# SchematicPowerSupply_V1.net
KiCad netlist of a schematic drawn in Altium Designer
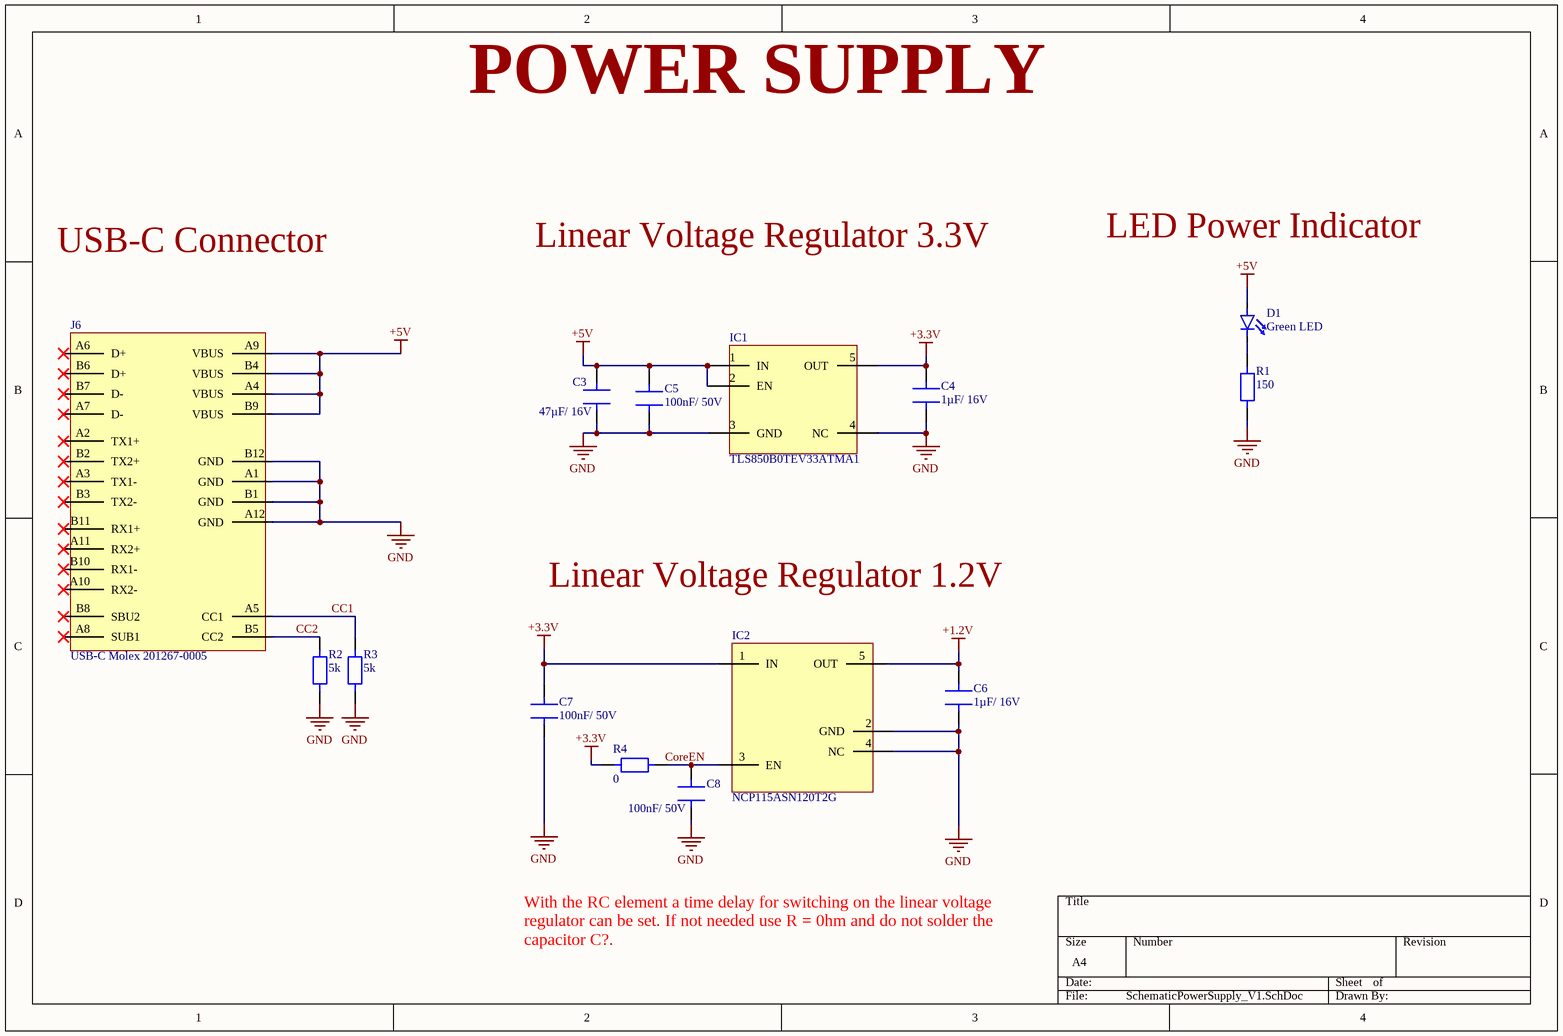
[diagram p0: SchematicPowerSupply_V1.SchDoc]

(export (version "E")
  (design (tool "Eeschema 10.0.6"))
  (components
    (comp (ref "C3")
      (value "47µF/ 16V")
      (footprint "C1210")
      (description "C1210")
      (libsource (lib "upbracing_library") (part "C 47µF/ 16V"))
    )
    (comp (ref "C4")
      (value "1µF/ 16V")
      (footprint "C0603")
      (description "C0603/C0805")
      (libsource (lib "upbracing_library") (part "C 1µF/ 16V"))
    )
    (comp (ref "C5")
      (value "100nF/ 50V")
      (footprint "C0603")
      (description "C0603/C0805")
      (libsource (lib "upbracing_library") (part "C 100nF/ 50V"))
    )
    (comp (ref "C6")
      (value "1µF/ 16V")
      (footprint "C0603")
      (description "C0603/C0805")
      (libsource (lib "upbracing_library") (part "C 1µF/ 16V"))
    )
    (comp (ref "C7")
      (value "100nF/ 50V")
      (footprint "C0603")
      (description "C0603/C0805")
      (libsource (lib "upbracing_library") (part "C 100nF/ 50V"))
    )
    (comp (ref "C8")
      (value "100nF/ 50V")
      (footprint "C0603")
      (description "C0603/C0805")
      (libsource (lib "upbracing_library") (part "C 100nF/ 50V"))
    )
    (comp (ref "D1")
      (value "Green LED")
      (footprint "LED_0805")
      (description "Status LED")
      (libsource (lib "upbracing_library") (part "LED 0805"))
    )
    (comp (ref "IC1")
      (value "TLS850B0TEV33ATMA1")
      (footprint "TO-252-5")
      (description "Input 3-40V, Output 3.3V")
      (libsource (lib "upbracing_library") (part "TLS850B0TEV33ATMA1"))
    )
    (comp (ref "IC2")
      (value "NCP115ASN120T2G")
      (footprint "TSOP-5")
      (description "Input 1.7V-5.5V, Ouput 1.2V")
      (libsource (lib "upbracing_library") (part "NCP115ASN120T2G"))
    )
    (comp (ref "J6")
      (value "USB-C Molex 201267-0005")
      (footprint "USB-C Molex 2012670005")
      (libsource (lib "upbracing_library") (part "USB-C Molex 201267-0005"))
    )
    (comp (ref "R1")
      (value "150")
      (footprint "R0603")
      (description "0603/0805")
      (libsource (lib "upbracing_library") (part "RES_150"))
    )
    (comp (ref "R2")
      (value "5k")
      (footprint "R0603")
      (description "0603/0805")
      (libsource (lib "upbracing_library") (part "RES_5k"))
    )
    (comp (ref "R3")
      (value "5k")
      (footprint "R0603")
      (description "0603/0805")
      (libsource (lib "upbracing_library") (part "RES_5k"))
    )
    (comp (ref "R4")
      (value "0")
      (footprint "R0603")
      (description "0603/0805")
      (libsource (lib "upbracing_library") (part "RES_0"))
    )
  )
  (nets
    (net (code "1") (name "+1.2V") (class "Default")
      (node (ref "C6") (pin "2") (pinfunction "2_2") (pintype "passive"))
      (node (ref "IC2") (pin "5") (pinfunction "OUT_5") (pintype "passive"))
    )
    (net (code "2") (name "+3.3V") (class "Default")
      (node (ref "C4") (pin "2") (pinfunction "2_2") (pintype "passive"))
      (node (ref "C7") (pin "2") (pinfunction "2_2") (pintype "passive"))
      (node (ref "IC1") (pin "5") (pinfunction "OUT_5") (pintype "passive"))
      (node (ref "IC2") (pin "1") (pinfunction "IN_1") (pintype "passive"))
      (node (ref "R4") (pin "2") (pinfunction "2_2") (pintype "passive"))
    )
    (net (code "3") (name "+5V") (class "Default")
      (node (ref "C3") (pin "2") (pinfunction "2_2") (pintype "passive"))
      (node (ref "C5") (pin "2") (pinfunction "2_2") (pintype "passive"))
      (node (ref "D1") (pin "1") (pinfunction "1_1") (pintype "passive"))
      (node (ref "IC1") (pin "1") (pinfunction "IN_1") (pintype "passive"))
      (node (ref "IC1") (pin "2") (pinfunction "EN_2") (pintype "passive"))
      (node (ref "J6") (pin "A4") (pinfunction "VBUS_A4") (pintype "passive"))
      (node (ref "J6") (pin "A9") (pinfunction "VBUS_A9") (pintype "passive"))
      (node (ref "J6") (pin "B4") (pinfunction "VBUS_B4") (pintype "passive"))
      (node (ref "J6") (pin "B9") (pinfunction "VBUS_B9") (pintype "passive"))
    )
    (net (code "4") (name "/CC1") (class "Default")
      (node (ref "J6") (pin "A5") (pinfunction "CC1_A5") (pintype "passive"))
      (node (ref "R3") (pin "2") (pinfunction "2_2") (pintype "passive"))
    )
    (net (code "5") (name "/CC2") (class "Default")
      (node (ref "J6") (pin "B5") (pinfunction "CC2_B5") (pintype "passive"))
      (node (ref "R2") (pin "2") (pinfunction "2_2") (pintype "passive"))
    )
    (net (code "6") (name "/CoreEN") (class "Default")
      (node (ref "C8") (pin "2") (pinfunction "2_2") (pintype "passive"))
      (node (ref "IC2") (pin "3") (pinfunction "EN_3") (pintype "passive"))
      (node (ref "R4") (pin "1") (pinfunction "1_1") (pintype "passive"))
    )
    (net (code "7") (name "GND") (class "Default")
      (node (ref "C3") (pin "1") (pinfunction "1_1") (pintype "passive"))
      (node (ref "C4") (pin "1") (pinfunction "1_1") (pintype "passive"))
      (node (ref "C5") (pin "1") (pinfunction "1_1") (pintype "passive"))
      (node (ref "C6") (pin "1") (pinfunction "1_1") (pintype "passive"))
      (node (ref "C7") (pin "1") (pinfunction "1_1") (pintype "passive"))
      (node (ref "C8") (pin "1") (pinfunction "1_1") (pintype "passive"))
      (node (ref "IC1") (pin "3") (pinfunction "GND_3") (pintype "passive"))
      (node (ref "IC1") (pin "4") (pinfunction "NC_4") (pintype "passive"))
      (node (ref "IC2") (pin "2") (pinfunction "GND_2") (pintype "passive"))
      (node (ref "IC2") (pin "4") (pinfunction "NC_4") (pintype "passive"))
      (node (ref "J6") (pin "A1") (pinfunction "GND_A1") (pintype "passive"))
      (node (ref "J6") (pin "A12") (pinfunction "GND_A12") (pintype "passive"))
      (node (ref "J6") (pin "B1") (pinfunction "GND_B1") (pintype "passive"))
      (node (ref "J6") (pin "B12") (pinfunction "GND_B12") (pintype "passive"))
      (node (ref "R1") (pin "1") (pinfunction "1_1") (pintype "passive"))
      (node (ref "R2") (pin "1") (pinfunction "1_1") (pintype "passive"))
      (node (ref "R3") (pin "1") (pinfunction "1_1") (pintype "passive"))
    )
    (net (code "8") (name "Net-(D1-Pad2)") (class "Default")
      (node (ref "D1") (pin "2") (pinfunction "2_2") (pintype "passive"))
      (node (ref "R1") (pin "2") (pinfunction "2_2") (pintype "passive"))
    )
    (net (code "9") (name "unconnected-(J6-D+-PadA6)") (class "Default")
      (node (ref "J6") (pin "A6") (pinfunction "D+_A6") (pintype "passive+no_connect"))
    )
    (net (code "10") (name "unconnected-(J6-D+-PadB6)") (class "Default")
      (node (ref "J6") (pin "B6") (pinfunction "D+_B6") (pintype "passive+no_connect"))
    )
    (net (code "11") (name "unconnected-(J6-D--PadA7)") (class "Default")
      (node (ref "J6") (pin "A7") (pinfunction "D-_A7") (pintype "passive+no_connect"))
    )
    (net (code "12") (name "unconnected-(J6-D--PadB7)") (class "Default")
      (node (ref "J6") (pin "B7") (pinfunction "D-_B7") (pintype "passive+no_connect"))
    )
    (net (code "13") (name "unconnected-(J6-RX1+-PadB11)") (class "Default")
      (node (ref "J6") (pin "B11") (pinfunction "RX1+_B11") (pintype "passive+no_connect"))
    )
    (net (code "14") (name "unconnected-(J6-RX1--PadB10)") (class "Default")
      (node (ref "J6") (pin "B10") (pinfunction "RX1-_B10") (pintype "passive+no_connect"))
    )
    (net (code "15") (name "unconnected-(J6-RX2+-PadA11)") (class "Default")
      (node (ref "J6") (pin "A11") (pinfunction "RX2+_A11") (pintype "passive+no_connect"))
    )
    (net (code "16") (name "unconnected-(J6-RX2--PadA10)") (class "Default")
      (node (ref "J6") (pin "A10") (pinfunction "RX2-_A10") (pintype "passive+no_connect"))
    )
    (net (code "17") (name "unconnected-(J6-SBU2-PadB8)") (class "Default")
      (node (ref "J6") (pin "B8") (pinfunction "SBU2_B8") (pintype "passive+no_connect"))
    )
    (net (code "18") (name "unconnected-(J6-SUB1-PadA8)") (class "Default")
      (node (ref "J6") (pin "A8") (pinfunction "SUB1_A8") (pintype "passive+no_connect"))
    )
    (net (code "19") (name "unconnected-(J6-TX1+-PadA2)") (class "Default")
      (node (ref "J6") (pin "A2") (pinfunction "TX1+_A2") (pintype "passive+no_connect"))
    )
    (net (code "20") (name "unconnected-(J6-TX1--PadA3)") (class "Default")
      (node (ref "J6") (pin "A3") (pinfunction "TX1-_A3") (pintype "passive+no_connect"))
    )
    (net (code "21") (name "unconnected-(J6-TX2+-PadB2)") (class "Default")
      (node (ref "J6") (pin "B2") (pinfunction "TX2+_B2") (pintype "passive+no_connect"))
    )
    (net (code "22") (name "unconnected-(J6-TX2--PadB3)") (class "Default")
      (node (ref "J6") (pin "B3") (pinfunction "TX2-_B3") (pintype "passive+no_connect"))
    )
  )
)
